# SCH_slime-vr_2022-05-18.net
KiCad netlist of a schematic drawn in EasyEDA
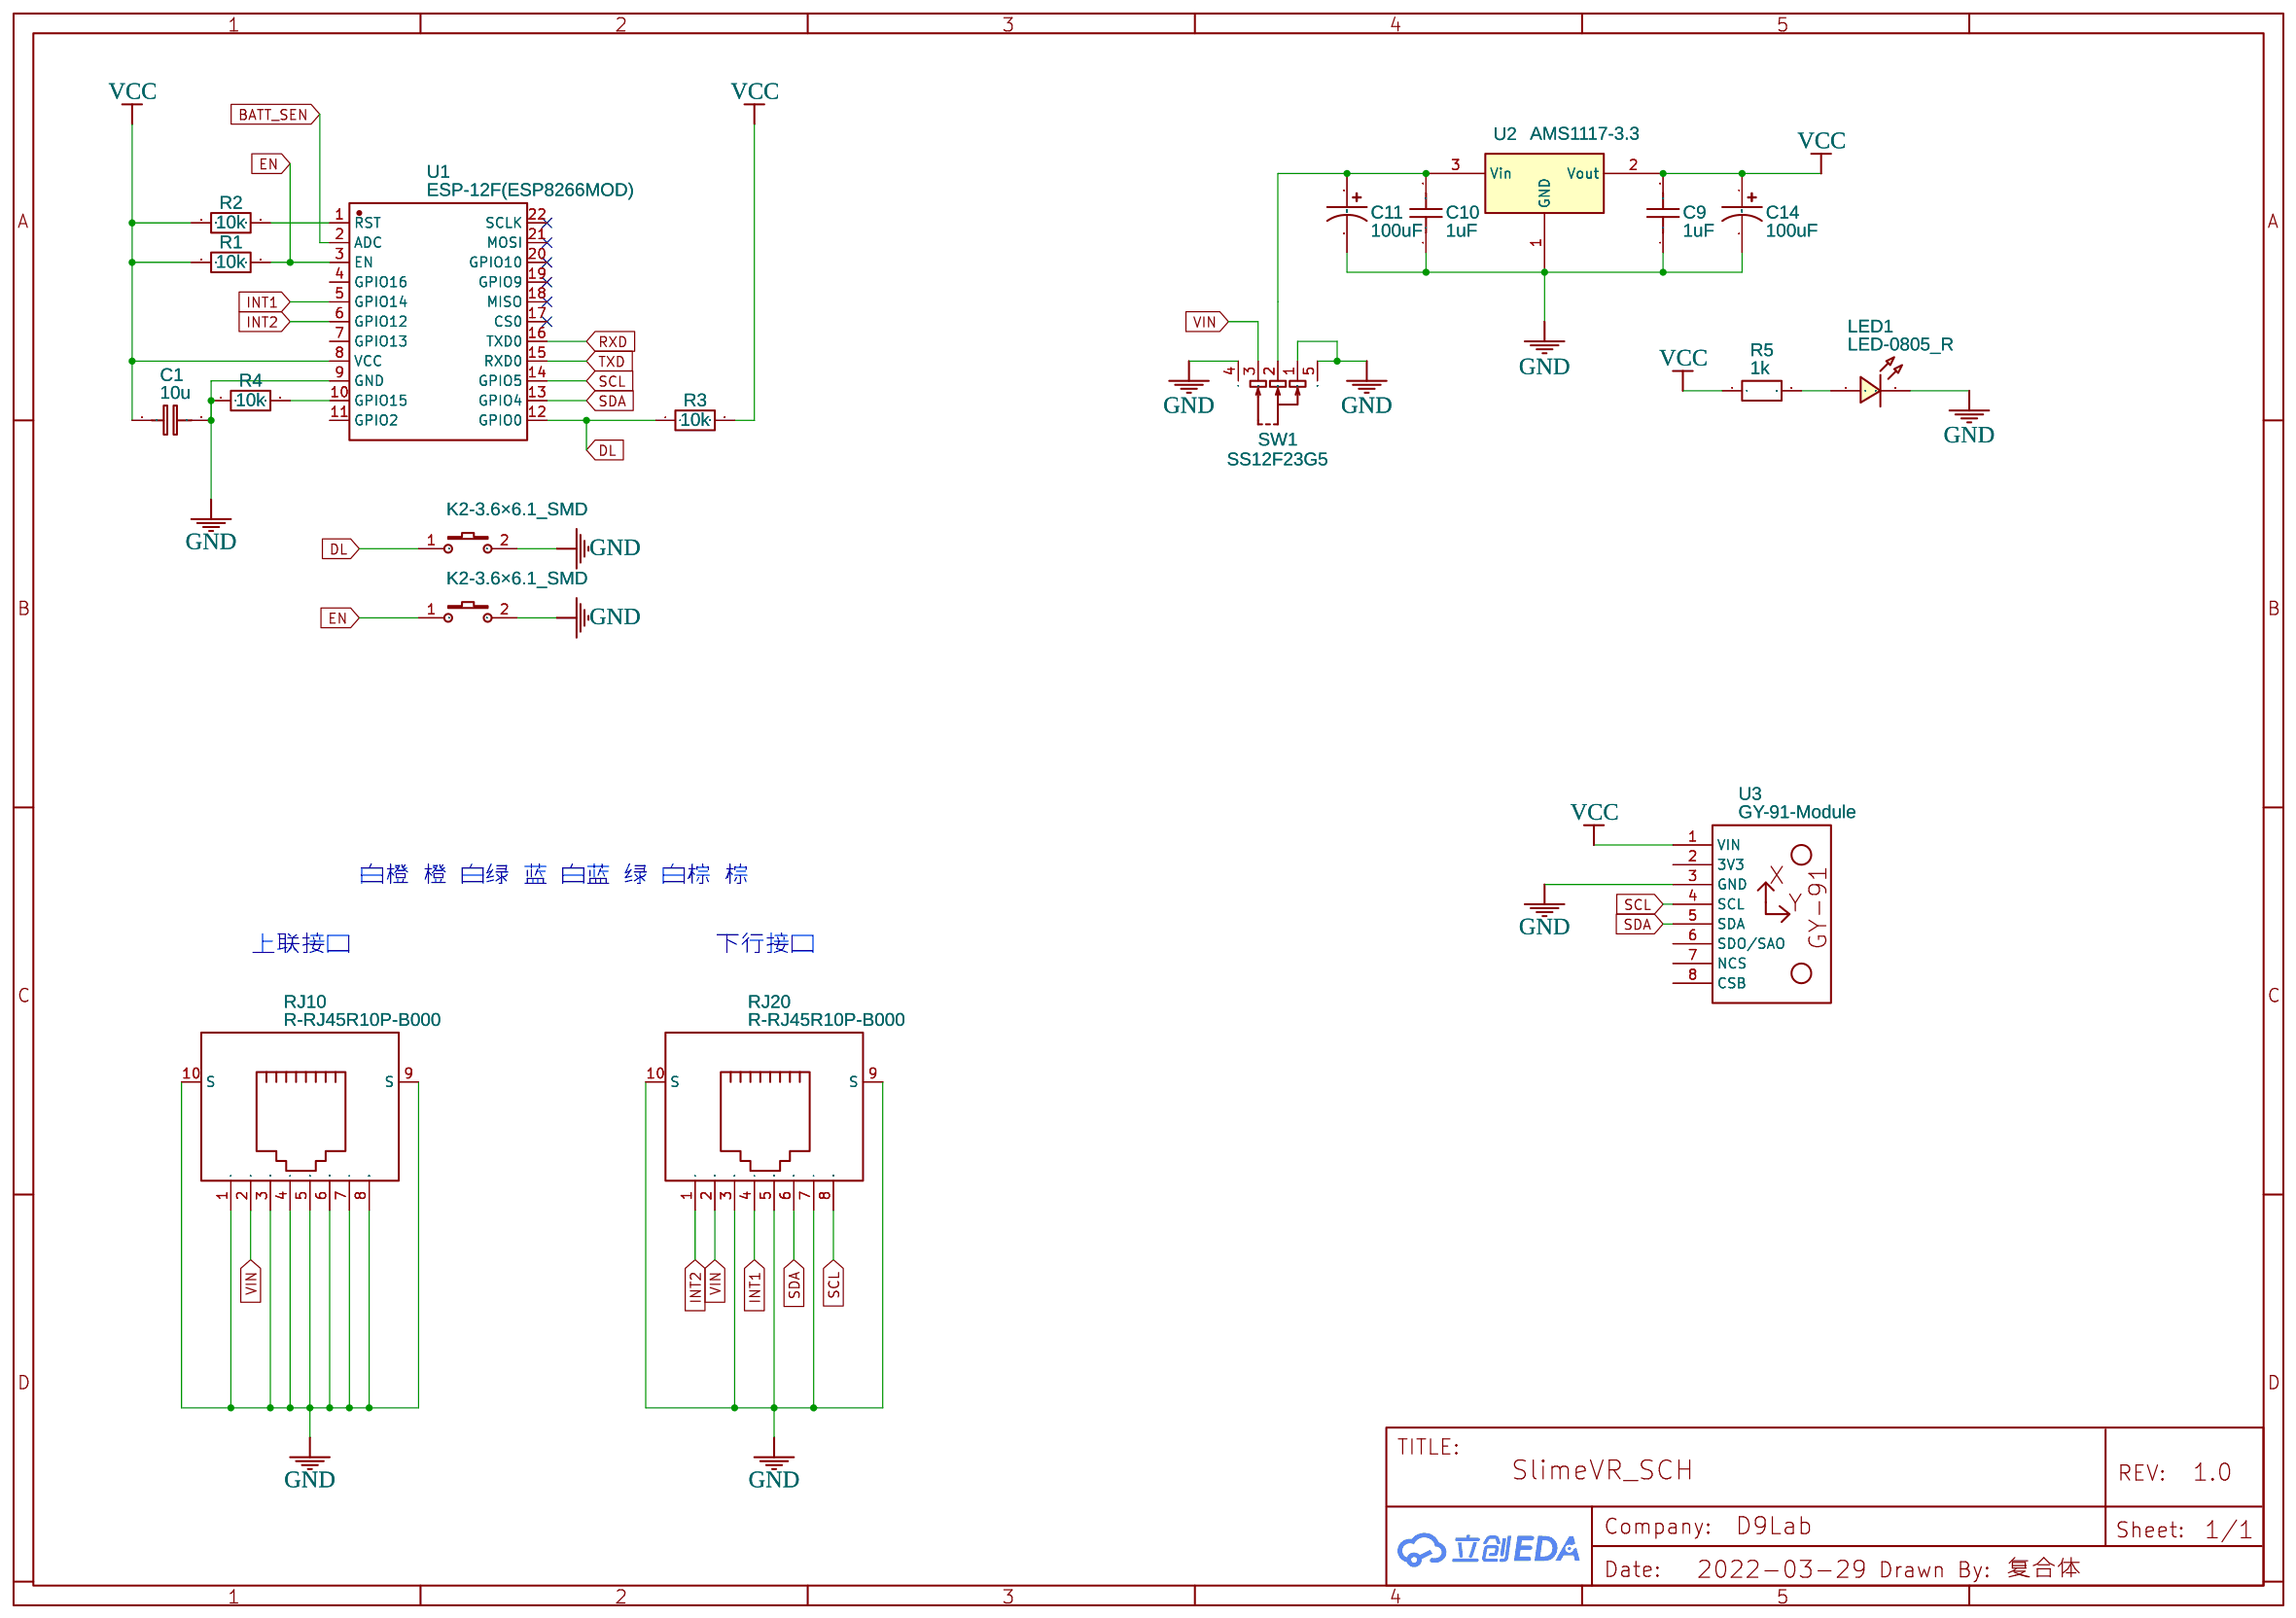
[diagram p0: SlimeVR_SCH]
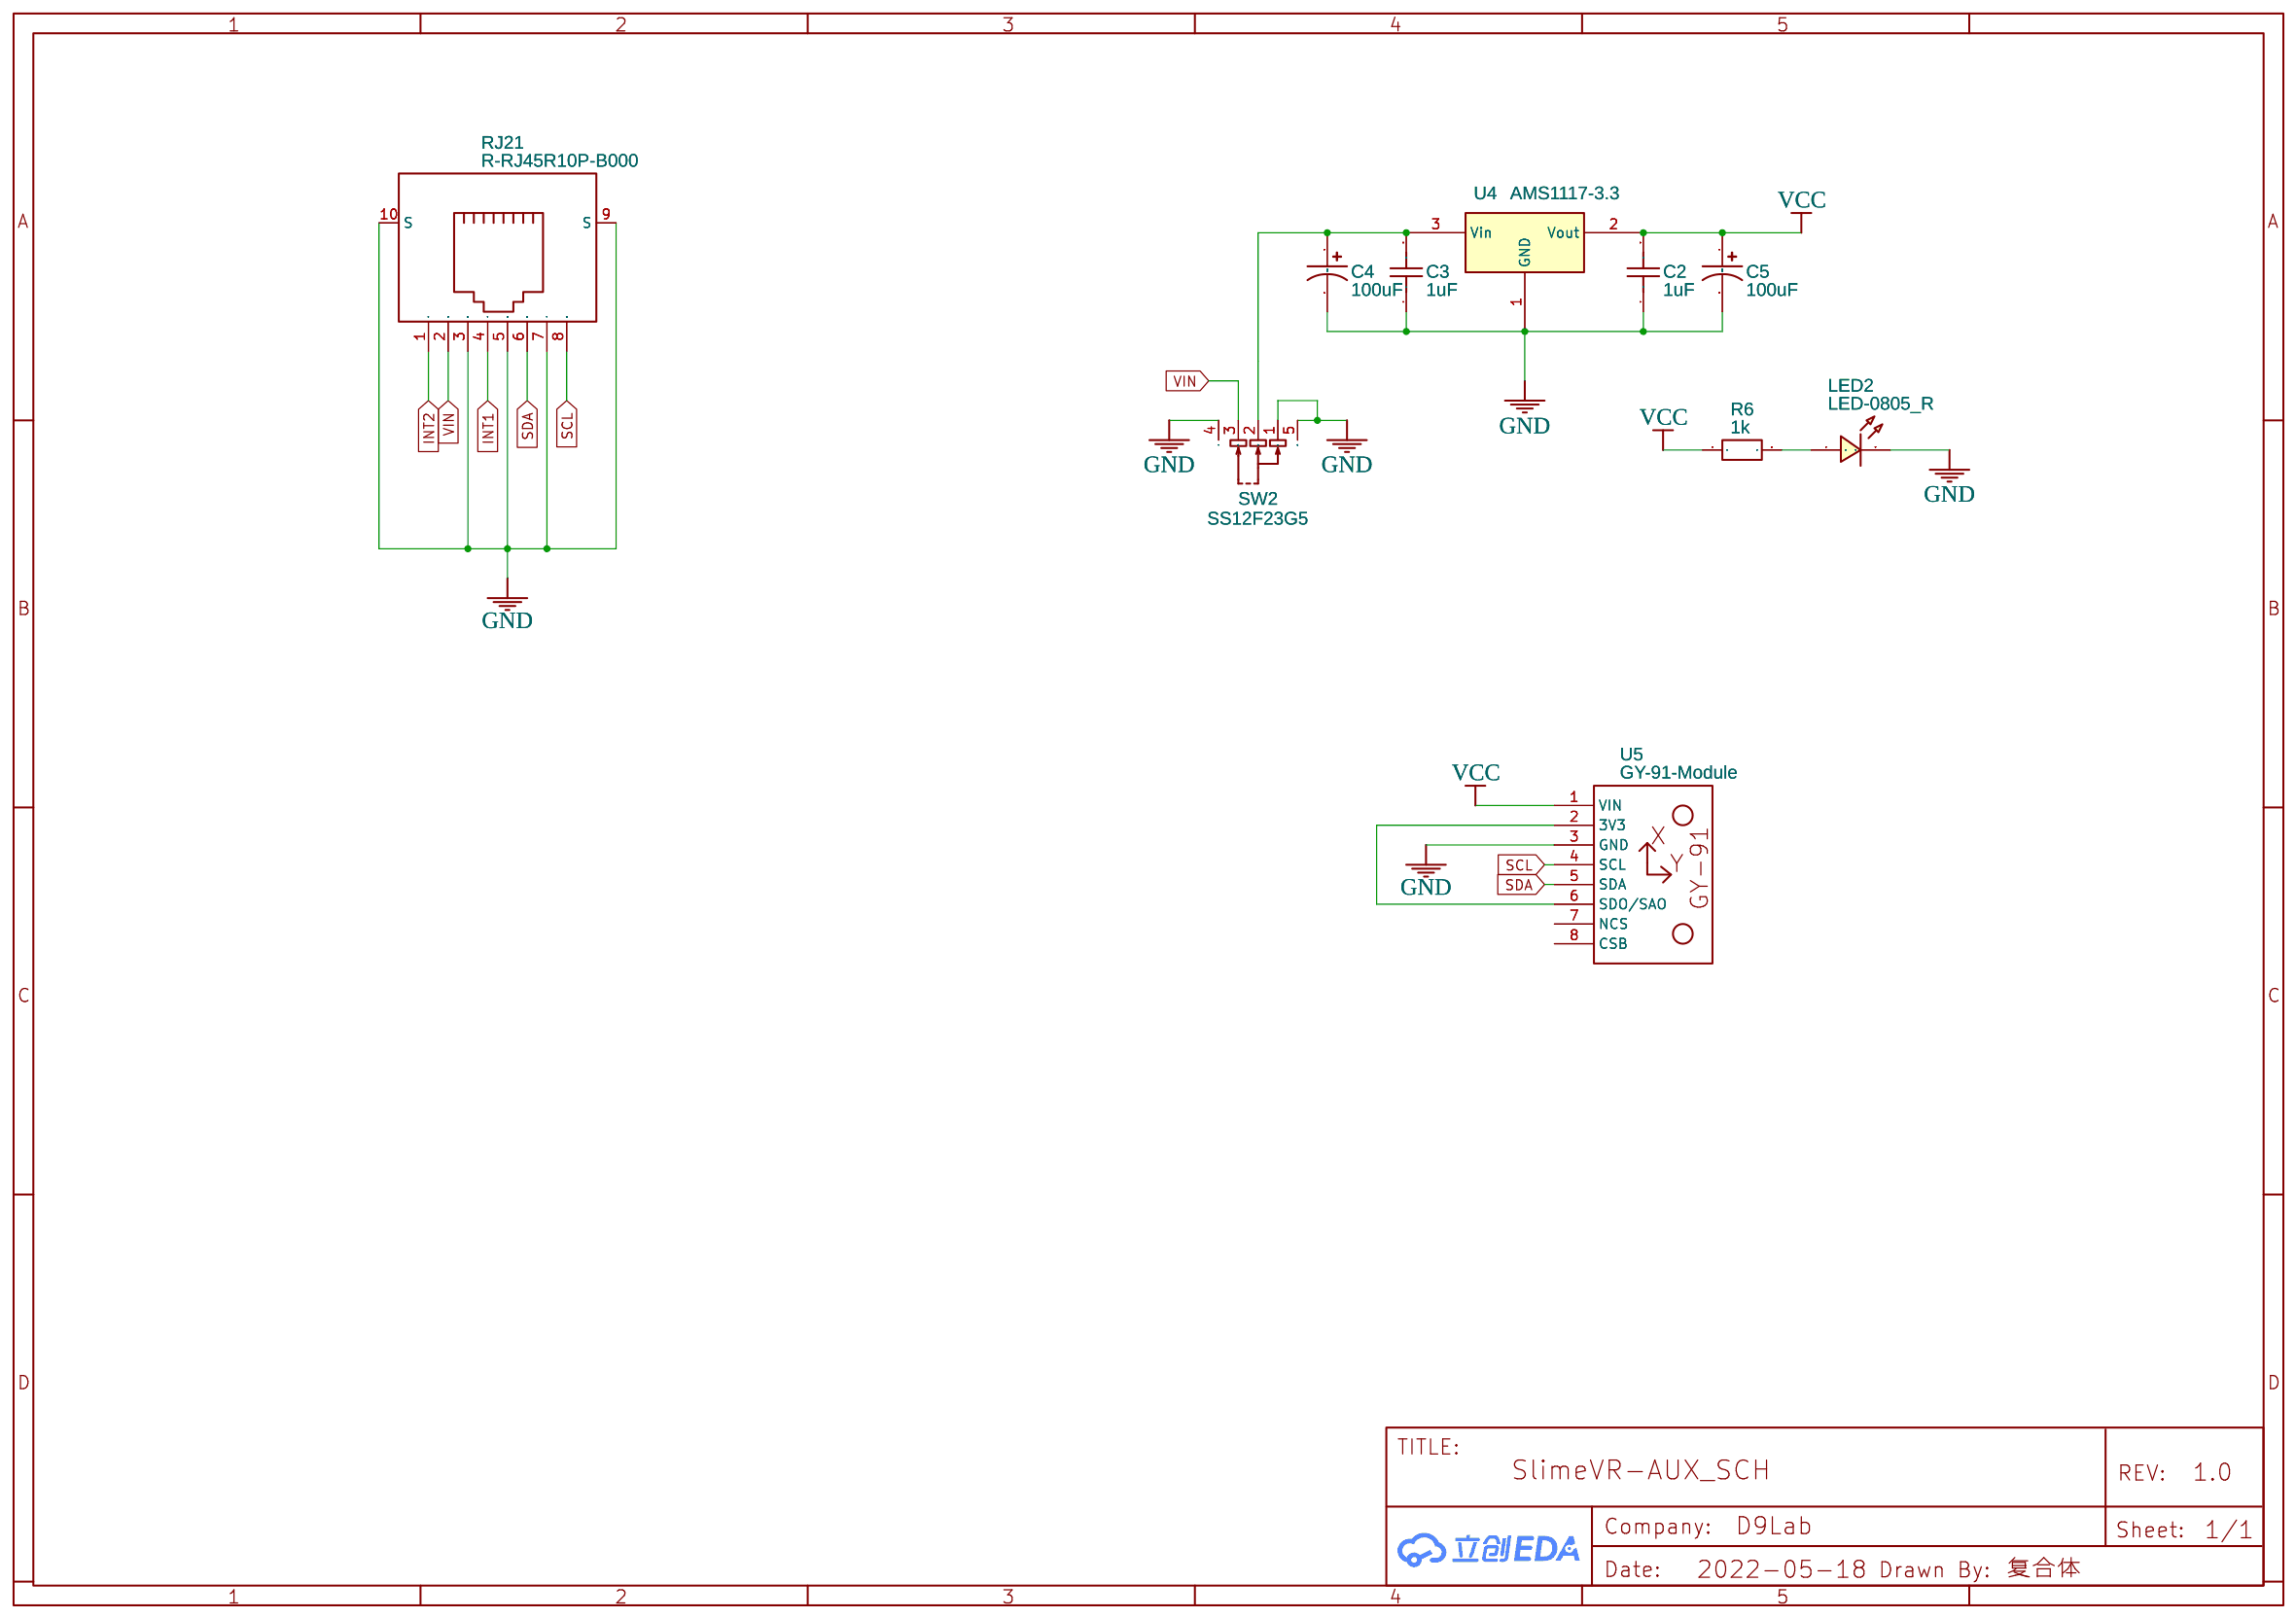
[diagram p1: SlimeVR-AUX_SCH]

(export (version "E")
  (design (tool "Eeschema 10.0.6"))
  (components
    (comp (ref "C1") (value "10u") (libsource (lib "") (part "C_0805_EU")))
    (comp (ref "C9") (value "1uF") (libsource (lib "") (part "C_0603_US")))
    (comp (ref "C10") (value "1uF") (libsource (lib "") (part "C_0603_US")))
    (comp (ref "C11") (value "100uF") (libsource (lib "") (part "C_Tan_SMD_A_US")))
    (comp (ref "C14") (value "100uF") (libsource (lib "") (part "C_Tan_SMD_A_US")))
    (comp (ref "DL")
      (value "K2-3.6×6.1_SMD")
      (fields
        (field (name "BOM_Manufacturer Part") "K2-1107ST-A4SW-06")
        (field (name "BOM_Supplier Part") "C118141")
      )
      (libsource (lib "") (part "K2-3.6×6.1_SMD_1"))
    )
    (comp (ref "EN")
      (value "K2-3.6×6.1_SMD")
      (fields
        (field (name "BOM_Manufacturer Part") "K2-1107ST-A4SW-06")
        (field (name "BOM_Supplier Part") "C118141")
      )
      (libsource (lib "") (part "K2-3.6×6.1_SMD"))
    )
    (comp (ref "LED1")
      (value "LED-0805_R")
      (fields
        (field (name "BOM_Manufacturer Part") "17-21SURC/S530-A3/TR8")
        (field (name "BOM_Supplier Part") "C72037")
      )
      (libsource (lib "") (part "LED-0805_R"))
    )
    (comp (ref "R1") (value "10k") (libsource (lib "") (part "R_0805_EU")))
    (comp (ref "R2") (value "10k") (libsource (lib "") (part "R_0805_EU")))
    (comp (ref "R3") (value "10k") (libsource (lib "") (part "R_0805_EU")))
    (comp (ref "R4") (value "10k") (libsource (lib "") (part "R_0805_EU")))
    (comp (ref "R5") (value "1k") (libsource (lib "") (part "R_0805_EU")))
    (comp (ref "RJ10")
      (value "R-RJ45R10P-B000")
      (fields (field (name "BOM_Supplier Part") "C386758"))
      (libsource (lib "") (part "R-RJ45R10P-B000"))
    )
    (comp (ref "RJ20")
      (value "R-RJ45R10P-B000")
      (fields (field (name "BOM_Supplier Part") "C386758"))
      (libsource (lib "") (part "R-RJ45R10P-B000"))
    )
    (comp (ref "SW1")
      (value "SS12F23G5")
      (fields (field (name "BOM_Supplier Part") "C2887262"))
      (libsource (lib "") (part "SS12F23G5"))
    )
    (comp (ref "U1")
      (value "ESP-12F(ESP8266MOD)")
      (fields (field (name "BOM_Supplier Part") "C82891"))
      (libsource (lib "") (part "ESP-12F(ESP8266MOD)"))
    )
    (comp (ref "U2")
      (value "AMS1117-3.3")
      (fields (field (name "BOM_Manufacturer Part") "?"))
      (libsource (lib "") (part "Unknown_775_-715"))
    )
    (comp (ref "U3")
      (value "GY-91-Module")
      (fields (field (name "BOM_Manufacturer Part") "GY-91 MPU9250 + BMP280"))
      (libsource (lib "") (part "GY-91-Module"))
    )
    (comp (ref "C2") (value "1uF") (libsource (lib "") (part "C_0603_US")))
    (comp (ref "C3") (value "1uF") (libsource (lib "") (part "C_0603_US")))
    (comp (ref "C4") (value "100uF") (libsource (lib "") (part "C_Tan_SMD_A_US")))
    (comp (ref "C5") (value "100uF") (libsource (lib "") (part "C_Tan_SMD_A_US")))
    (comp (ref "LED2")
      (value "LED-0805_R")
      (fields
        (field (name "BOM_Manufacturer Part") "17-21SURC/S530-A3/TR8")
        (field (name "BOM_Supplier Part") "C72037")
      )
      (libsource (lib "") (part "LED-0805_R"))
    )
    (comp (ref "R6") (value "1k") (libsource (lib "") (part "R_0805_EU")))
    (comp (ref "RJ21")
      (value "R-RJ45R10P-B000")
      (fields (field (name "BOM_Supplier Part") "C386758"))
      (libsource (lib "") (part "R-RJ45R10P-B000"))
    )
    (comp (ref "SW2")
      (value "SS12F23G5")
      (fields (field (name "BOM_Supplier Part") "C2887262"))
      (libsource (lib "") (part "SS12F23G5"))
    )
    (comp (ref "U4")
      (value "AMS1117-3.3")
      (fields (field (name "BOM_Manufacturer Part") "?"))
      (libsource (lib "") (part "Unknown_765_-685"))
    )
    (comp (ref "U5")
      (value "GY-91-Module")
      (fields (field (name "BOM_Manufacturer Part") "GY-91 MPU9250 + BMP280"))
      (libsource (lib "") (part "GY-91-Module"))
    )
  )
  (nets
    (net (code "1") (name "BATT_SEN") (class "Default")
      (node (ref "U1") (pin "2") (pinfunction "ADC_2") (pintype "unspecified"))
    )
    (net (code "2") (name "DL") (class "Default")
      (node (ref "DL") (pin "1") (pinfunction "1_1") (pintype "unspecified"))
      (node (ref "R3") (pin "1") (pinfunction "1_1") (pintype "unspecified"))
      (node (ref "U1") (pin "12") (pinfunction "GPIO0_12") (pintype "unspecified"))
    )
    (net (code "3") (name "EN") (class "Default")
      (node (ref "EN") (pin "1") (pinfunction "1_1") (pintype "unspecified"))
      (node (ref "R1") (pin "2") (pinfunction "2_2") (pintype "unspecified"))
      (node (ref "U1") (pin "3") (pinfunction "EN_3") (pintype "unspecified"))
    )
    (net (code "4") (name "GND") (class "Default")
      (node (ref "C1") (pin "2") (pinfunction "2_2") (pintype "unspecified"))
      (node (ref "C10") (pin "1") (pinfunction "1_1") (pintype "unspecified"))
      (node (ref "C11") (pin "2") (pinfunction "2_2") (pintype "unspecified"))
      (node (ref "C14") (pin "2") (pinfunction "2_2") (pintype "unspecified"))
      (node (ref "C2") (pin "1") (pinfunction "1_1") (pintype "unspecified"))
      (node (ref "C3") (pin "1") (pinfunction "1_1") (pintype "unspecified"))
      (node (ref "C4") (pin "2") (pinfunction "2_2") (pintype "unspecified"))
      (node (ref "C5") (pin "2") (pinfunction "2_2") (pintype "unspecified"))
      (node (ref "C9") (pin "1") (pinfunction "1_1") (pintype "unspecified"))
      (node (ref "DL") (pin "2") (pinfunction "2_2") (pintype "unspecified"))
      (node (ref "EN") (pin "2") (pinfunction "2_2") (pintype "unspecified"))
      (node (ref "LED1") (pin "2") (pinfunction "2_2") (pintype "unspecified"))
      (node (ref "LED2") (pin "2") (pinfunction "2_2") (pintype "unspecified"))
      (node (ref "R4") (pin "1") (pinfunction "1_1") (pintype "unspecified"))
      (node (ref "RJ10") (pin "1") (pinfunction "1_1") (pintype "unspecified"))
      (node (ref "RJ10") (pin "10") (pinfunction "S_10") (pintype "unspecified"))
      (node (ref "RJ10") (pin "3") (pinfunction "3_3") (pintype "unspecified"))
      (node (ref "RJ10") (pin "4") (pinfunction "4_4") (pintype "unspecified"))
      (node (ref "RJ10") (pin "5") (pinfunction "5_5") (pintype "unspecified"))
      (node (ref "RJ10") (pin "6") (pinfunction "6_6") (pintype "unspecified"))
      (node (ref "RJ10") (pin "7") (pinfunction "7_7") (pintype "unspecified"))
      (node (ref "RJ10") (pin "8") (pinfunction "8_8") (pintype "unspecified"))
      (node (ref "RJ10") (pin "9") (pinfunction "S_9") (pintype "unspecified"))
      (node (ref "RJ20") (pin "10") (pinfunction "S_10") (pintype "unspecified"))
      (node (ref "RJ20") (pin "3") (pinfunction "3_3") (pintype "unspecified"))
      (node (ref "RJ20") (pin "5") (pinfunction "5_5") (pintype "unspecified"))
      (node (ref "RJ20") (pin "7") (pinfunction "7_7") (pintype "unspecified"))
      (node (ref "RJ20") (pin "9") (pinfunction "S_9") (pintype "unspecified"))
      (node (ref "RJ21") (pin "10") (pinfunction "S_10") (pintype "unspecified"))
      (node (ref "RJ21") (pin "3") (pinfunction "3_3") (pintype "unspecified"))
      (node (ref "RJ21") (pin "5") (pinfunction "5_5") (pintype "unspecified"))
      (node (ref "RJ21") (pin "7") (pinfunction "7_7") (pintype "unspecified"))
      (node (ref "RJ21") (pin "9") (pinfunction "S_9") (pintype "unspecified"))
      (node (ref "SW1") (pin "1") (pinfunction "1_1") (pintype "unspecified"))
      (node (ref "SW1") (pin "4") (pinfunction "4_4") (pintype "unspecified"))
      (node (ref "SW1") (pin "5") (pinfunction "5_5") (pintype "unspecified"))
      (node (ref "SW2") (pin "1") (pinfunction "1_1") (pintype "unspecified"))
      (node (ref "SW2") (pin "4") (pinfunction "4_4") (pintype "unspecified"))
      (node (ref "SW2") (pin "5") (pinfunction "5_5") (pintype "unspecified"))
      (node (ref "U1") (pin "9") (pinfunction "GND_9") (pintype "unspecified"))
      (node (ref "U2") (pin "1") (pinfunction "GND_1") (pintype "unspecified"))
      (node (ref "U3") (pin "3") (pinfunction "GND_3") (pintype "unspecified"))
      (node (ref "U4") (pin "1") (pinfunction "GND_1") (pintype "unspecified"))
      (node (ref "U5") (pin "3") (pinfunction "GND_3") (pintype "unspecified"))
    )
    (net (code "5") (name "INT1") (class "Default")
      (node (ref "RJ20") (pin "4") (pinfunction "4_4") (pintype "unspecified"))
      (node (ref "RJ21") (pin "4") (pinfunction "4_4") (pintype "unspecified"))
      (node (ref "U1") (pin "5") (pinfunction "GPIO14_5") (pintype "unspecified"))
    )
    (net (code "6") (name "INT2") (class "Default")
      (node (ref "RJ20") (pin "1") (pinfunction "1_1") (pintype "unspecified"))
      (node (ref "RJ21") (pin "1") (pinfunction "1_1") (pintype "unspecified"))
      (node (ref "U1") (pin "6") (pinfunction "GPIO12_6") (pintype "unspecified"))
    )
    (net (code "7") (name "Net-(LED1-Pad1)") (class "Default")
      (node (ref "LED1") (pin "1") (pinfunction "1_1") (pintype "unspecified"))
      (node (ref "R5") (pin "2") (pinfunction "2_2") (pintype "unspecified"))
    )
    (net (code "8") (name "Net-(LED2-Pad1)") (class "Default")
      (node (ref "LED2") (pin "1") (pinfunction "1_1") (pintype "unspecified"))
      (node (ref "R6") (pin "2") (pinfunction "2_2") (pintype "unspecified"))
    )
    (net (code "9") (name "Net-(U1-GPIO15)") (class "Default")
      (node (ref "R4") (pin "2") (pinfunction "2_2") (pintype "unspecified"))
      (node (ref "U1") (pin "10") (pinfunction "GPIO15_10") (pintype "unspecified"))
    )
    (net (code "10") (name "Net-(U1-RST)") (class "Default")
      (node (ref "R2") (pin "2") (pinfunction "2_2") (pintype "unspecified"))
      (node (ref "U1") (pin "1") (pinfunction "RST_1") (pintype "unspecified"))
    )
    (net (code "11") (name "Net-(U2-Vin)") (class "Default")
      (node (ref "C10") (pin "2") (pinfunction "2_2") (pintype "unspecified"))
      (node (ref "C11") (pin "1") (pinfunction "1_1") (pintype "unspecified"))
      (node (ref "SW1") (pin "2") (pinfunction "2_2") (pintype "unspecified"))
      (node (ref "U2") (pin "3") (pinfunction "Vin_3") (pintype "unspecified"))
    )
    (net (code "12") (name "Net-(U4-Vin)") (class "Default")
      (node (ref "C3") (pin "2") (pinfunction "2_2") (pintype "unspecified"))
      (node (ref "C4") (pin "1") (pinfunction "1_1") (pintype "unspecified"))
      (node (ref "SW2") (pin "2") (pinfunction "2_2") (pintype "unspecified"))
      (node (ref "U4") (pin "3") (pinfunction "Vin_3") (pintype "unspecified"))
    )
    (net (code "13") (name "Net-(U5-3V3)") (class "Default")
      (node (ref "U5") (pin "2") (pinfunction "3V3_2") (pintype "unspecified"))
      (node (ref "U5") (pin "6") (pinfunction "SDO/SAO_6") (pintype "unspecified"))
    )
    (net (code "14") (name "RXD") (class "Default")
      (node (ref "U1") (pin "16") (pinfunction "TXD0_16") (pintype "unspecified"))
    )
    (net (code "15") (name "SCL") (class "Default")
      (node (ref "RJ20") (pin "8") (pinfunction "8_8") (pintype "unspecified"))
      (node (ref "RJ21") (pin "8") (pinfunction "8_8") (pintype "unspecified"))
      (node (ref "U1") (pin "14") (pinfunction "GPIO5_14") (pintype "unspecified"))
      (node (ref "U3") (pin "4") (pinfunction "SCL_4") (pintype "unspecified"))
      (node (ref "U5") (pin "4") (pinfunction "SCL_4") (pintype "unspecified"))
    )
    (net (code "16") (name "SDA") (class "Default")
      (node (ref "RJ20") (pin "6") (pinfunction "6_6") (pintype "unspecified"))
      (node (ref "RJ21") (pin "6") (pinfunction "6_6") (pintype "unspecified"))
      (node (ref "U1") (pin "13") (pinfunction "GPIO4_13") (pintype "unspecified"))
      (node (ref "U3") (pin "5") (pinfunction "SDA_5") (pintype "unspecified"))
      (node (ref "U5") (pin "5") (pinfunction "SDA_5") (pintype "unspecified"))
    )
    (net (code "17") (name "TXD") (class "Default")
      (node (ref "U1") (pin "15") (pinfunction "RXD0_15") (pintype "unspecified"))
    )
    (net (code "18") (name "VCC") (class "Default")
      (node (ref "C1") (pin "1") (pinfunction "1_1") (pintype "unspecified"))
      (node (ref "C14") (pin "1") (pinfunction "1_1") (pintype "unspecified"))
      (node (ref "C2") (pin "2") (pinfunction "2_2") (pintype "unspecified"))
      (node (ref "C5") (pin "1") (pinfunction "1_1") (pintype "unspecified"))
      (node (ref "C9") (pin "2") (pinfunction "2_2") (pintype "unspecified"))
      (node (ref "R1") (pin "1") (pinfunction "1_1") (pintype "unspecified"))
      (node (ref "R2") (pin "1") (pinfunction "1_1") (pintype "unspecified"))
      (node (ref "R3") (pin "2") (pinfunction "2_2") (pintype "unspecified"))
      (node (ref "R5") (pin "1") (pinfunction "1_1") (pintype "unspecified"))
      (node (ref "R6") (pin "1") (pinfunction "1_1") (pintype "unspecified"))
      (node (ref "U1") (pin "8") (pinfunction "VCC_8") (pintype "unspecified"))
      (node (ref "U2") (pin "2") (pinfunction "Vout_2") (pintype "unspecified"))
      (node (ref "U3") (pin "1") (pinfunction "VIN_1") (pintype "unspecified"))
      (node (ref "U4") (pin "2") (pinfunction "Vout_2") (pintype "unspecified"))
      (node (ref "U5") (pin "1") (pinfunction "VIN_1") (pintype "unspecified"))
    )
    (net (code "19") (name "VIN") (class "Default")
      (node (ref "RJ10") (pin "2") (pinfunction "2_2") (pintype "unspecified"))
      (node (ref "RJ20") (pin "2") (pinfunction "2_2") (pintype "unspecified"))
      (node (ref "RJ21") (pin "2") (pinfunction "2_2") (pintype "unspecified"))
      (node (ref "SW1") (pin "3") (pinfunction "3_3") (pintype "unspecified"))
      (node (ref "SW2") (pin "3") (pinfunction "3_3") (pintype "unspecified"))
    )
    (net (code "20") (name "unconnected-(U1-CS0-Pad17)") (class "Default")
      (node (ref "U1") (pin "17") (pinfunction "CS0_17") (pintype "unspecified+no_connect"))
    )
    (net (code "21") (name "unconnected-(U1-GPIO2-Pad11)") (class "Default")
      (node (ref "U1") (pin "11") (pinfunction "GPIO2_11") (pintype "unspecified"))
    )
    (net (code "22") (name "unconnected-(U1-GPIO9-Pad19)") (class "Default")
      (node (ref "U1") (pin "19") (pinfunction "GPIO9_19") (pintype "unspecified+no_connect"))
    )
    (net (code "23") (name "unconnected-(U1-GPIO10-Pad20)") (class "Default")
      (node (ref "U1") (pin "20") (pinfunction "GPIO10_20") (pintype "unspecified+no_connect"))
    )
    (net (code "24") (name "unconnected-(U1-GPIO13-Pad7)") (class "Default")
      (node (ref "U1") (pin "7") (pinfunction "GPIO13_7") (pintype "unspecified"))
    )
    (net (code "25") (name "unconnected-(U1-GPIO16-Pad4)") (class "Default")
      (node (ref "U1") (pin "4") (pinfunction "GPIO16_4") (pintype "unspecified"))
    )
    (net (code "26") (name "unconnected-(U1-MISO-Pad18)") (class "Default")
      (node (ref "U1") (pin "18") (pinfunction "MISO_18") (pintype "unspecified+no_connect"))
    )
    (net (code "27") (name "unconnected-(U1-MOSI-Pad21)") (class "Default")
      (node (ref "U1") (pin "21") (pinfunction "MOSI_21") (pintype "unspecified+no_connect"))
    )
    (net (code "28") (name "unconnected-(U1-SCLK-Pad22)") (class "Default")
      (node (ref "U1") (pin "22") (pinfunction "SCLK_22") (pintype "unspecified+no_connect"))
    )
    (net (code "29") (name "unconnected-(U3-3V3-Pad2)") (class "Default")
      (node (ref "U3") (pin "2") (pinfunction "3V3_2") (pintype "unspecified"))
    )
    (net (code "30") (name "unconnected-(U3-CSB-Pad8)") (class "Default")
      (node (ref "U3") (pin "8") (pinfunction "CSB_8") (pintype "unspecified"))
    )
    (net (code "31") (name "unconnected-(U3-NCS-Pad7)") (class "Default")
      (node (ref "U3") (pin "7") (pinfunction "NCS_7") (pintype "unspecified"))
    )
    (net (code "32") (name "unconnected-(U3-SDO{slash}SAO-Pad6)") (class "Default")
      (node (ref "U3") (pin "6") (pinfunction "SDO/SAO_6") (pintype "unspecified"))
    )
    (net (code "33") (name "unconnected-(U5-CSB-Pad8)") (class "Default")
      (node (ref "U5") (pin "8") (pinfunction "CSB_8") (pintype "unspecified"))
    )
    (net (code "34") (name "unconnected-(U5-NCS-Pad7)") (class "Default")
      (node (ref "U5") (pin "7") (pinfunction "NCS_7") (pintype "unspecified"))
    )
  )
)
